# Sam7s64.net
KiCad netlist of a schematic drawn in EAGLE
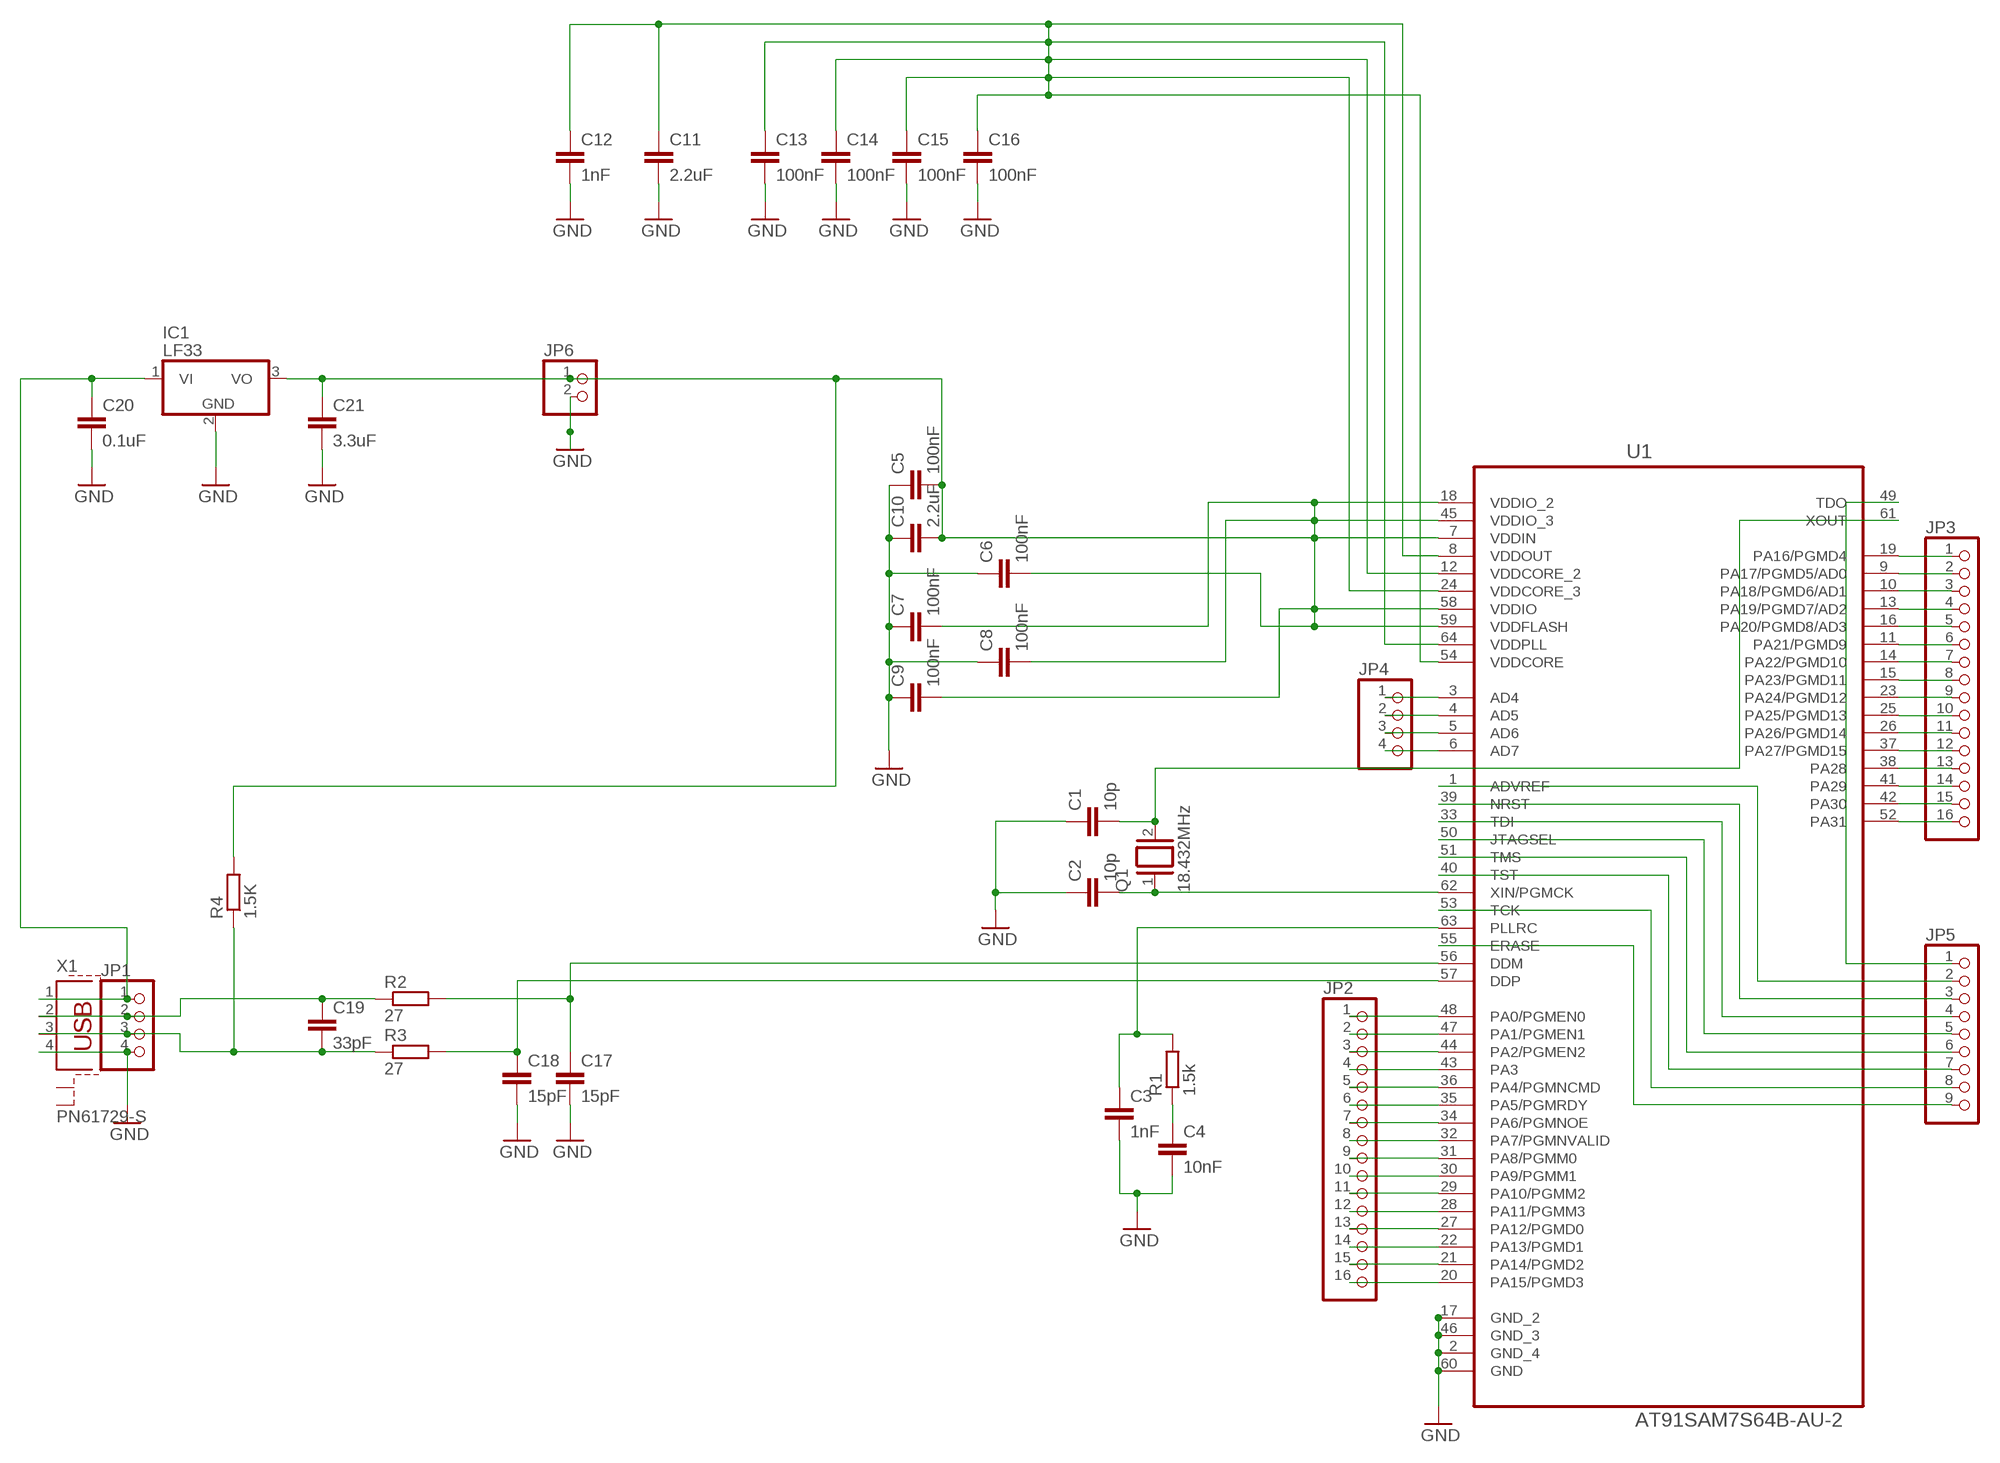
[diagram p0: schematic, sheet 1]

(export (version "E")
  (design (tool "Eeschema 10.0.6"))
  (components
    (comp (ref "C1")
      (value "10p")
      (footprint "eagle-import:C5B2.5")
      (libsource (lib "eagle-import") (part "C5/2.5"))
    )
    (comp (ref "C2")
      (value "10p")
      (footprint "eagle-import:C5B2.5")
      (libsource (lib "eagle-import") (part "C5/2.5"))
    )
    (comp (ref "C3")
      (value "1nF")
      (footprint "eagle-import:C5B2.5")
      (libsource (lib "eagle-import") (part "C5/2.5"))
    )
    (comp (ref "C4")
      (value "10nF")
      (footprint "eagle-import:C5B2.5")
      (libsource (lib "eagle-import") (part "C5/2.5"))
    )
    (comp (ref "C5")
      (value "100nF")
      (footprint "eagle-import:C5B2.5")
      (libsource (lib "eagle-import") (part "C5/2.5"))
    )
    (comp (ref "C6")
      (value "100nF")
      (footprint "eagle-import:C5B2.5")
      (libsource (lib "eagle-import") (part "C5/2.5"))
    )
    (comp (ref "C7")
      (value "100nF")
      (footprint "eagle-import:C5B2.5")
      (libsource (lib "eagle-import") (part "C5/2.5"))
    )
    (comp (ref "C8")
      (value "100nF")
      (footprint "eagle-import:C5B2.5")
      (libsource (lib "eagle-import") (part "C5/2.5"))
    )
    (comp (ref "C9")
      (value "100nF")
      (footprint "eagle-import:C5B2.5")
      (libsource (lib "eagle-import") (part "C5/2.5"))
    )
    (comp (ref "C10")
      (value "2.2uF")
      (footprint "eagle-import:C2.5-2")
      (libsource (lib "eagle-import") (part "C2.5/2"))
    )
    (comp (ref "C11")
      (value "2.2uF")
      (footprint "eagle-import:C2.5-2")
      (libsource (lib "eagle-import") (part "C2.5/2"))
    )
    (comp (ref "C12")
      (value "1nF")
      (footprint "eagle-import:C5B2.5")
      (libsource (lib "eagle-import") (part "C5/2.5"))
    )
    (comp (ref "C13")
      (value "100nF")
      (footprint "eagle-import:C5B2.5")
      (libsource (lib "eagle-import") (part "C5/2.5"))
    )
    (comp (ref "C14")
      (value "100nF")
      (footprint "eagle-import:C5B2.5")
      (libsource (lib "eagle-import") (part "C5/2.5"))
    )
    (comp (ref "C15")
      (value "100nF")
      (footprint "eagle-import:C5B2.5")
      (libsource (lib "eagle-import") (part "C5/2.5"))
    )
    (comp (ref "C16")
      (value "100nF")
      (footprint "eagle-import:C5B2.5")
      (libsource (lib "eagle-import") (part "C5/2.5"))
    )
    (comp (ref "C17")
      (value "15pF")
      (footprint "eagle-import:C5B2.5")
      (libsource (lib "eagle-import") (part "C5/2.5"))
    )
    (comp (ref "C18")
      (value "15pF")
      (footprint "eagle-import:C5B2.5")
      (libsource (lib "eagle-import") (part "C5/2.5"))
    )
    (comp (ref "C19")
      (value "33pF")
      (footprint "eagle-import:C5B2.5")
      (libsource (lib "eagle-import") (part "C5/2.5"))
    )
    (comp (ref "C20")
      (value "0.1uF")
      (footprint "eagle-import:C2.5-2")
      (libsource (lib "eagle-import") (part "C2.5/2"))
    )
    (comp (ref "C21")
      (value "3.3uF")
      (footprint "eagle-import:C2.5-2")
      (libsource (lib "eagle-import") (part "C2.5/2"))
    )
    (comp (ref "IC1")
      (value "LF33")
      (footprint "eagle-import:TO220V")
      (libsource (lib "eagle-import") (part "78TV05"))
    )
    (comp (ref "JP1")
      (value "PINHD-1X4")
      (footprint "eagle-import:1X04")
      (libsource (lib "eagle-import") (part "PINHD-1X4"))
    )
    (comp (ref "JP2")
      (value "PINHD-1X16")
      (footprint "eagle-import:1X16")
      (libsource (lib "eagle-import") (part "PINHD-1X16"))
    )
    (comp (ref "JP3")
      (value "PINHD-1X16")
      (footprint "eagle-import:1X16")
      (libsource (lib "eagle-import") (part "PINHD-1X16"))
    )
    (comp (ref "JP4")
      (value "PINHD-1X4")
      (footprint "eagle-import:1X04")
      (libsource (lib "eagle-import") (part "PINHD-1X4"))
    )
    (comp (ref "JP5")
      (value "PINHD-1X9")
      (footprint "eagle-import:1X09")
      (libsource (lib "eagle-import") (part "PINHD-1X9"))
    )
    (comp (ref "JP6")
      (value "PINHD-1X2")
      (footprint "eagle-import:1X02")
      (libsource (lib "eagle-import") (part "PINHD-1X2"))
    )
    (comp (ref "Q1")
      (value "18.432MHz")
      (footprint "eagle-import:QS")
      (libsource (lib "eagle-import") (part "XTAL/S"))
    )
    (comp (ref "R1")
      (value "1.5k")
      (footprint "eagle-import:0207_10")
      (libsource (lib "eagle-import") (part "R-EU_0207/10"))
    )
    (comp (ref "R2")
      (value "27")
      (footprint "eagle-import:0207_10")
      (libsource (lib "eagle-import") (part "R-EU_0207/10"))
    )
    (comp (ref "R3")
      (value "27")
      (footprint "eagle-import:0207_10")
      (libsource (lib "eagle-import") (part "R-EU_0207/10"))
    )
    (comp (ref "R4")
      (value "1.5K")
      (footprint "eagle-import:0207_10")
      (libsource (lib "eagle-import") (part "R-EU_0207/10"))
    )
    (comp (ref "U1")
      (value "AT91SAM7S64B-AU-2")
      (footprint "eagle-import:QFP50P1200X1200X160-64N")
      (fields (field (name "MPN") "AT91SAM7S64B-AU"))
      (libsource (lib "eagle-import") (part "AT91SAM7S64B-AU-2"))
    )
    (comp (ref "X1")
      (value "PN61729-S")
      (footprint "eagle-import:PN61729-S")
      (libsource (lib "eagle-import") (part "PN61729-S"))
    )
  )
  (nets
    (net (code "1") (name "GND") (class "Default")
      (node (ref "C1") (pin "1") (pinfunction "1_1") (pintype "passive"))
      (node (ref "C10") (pin "1") (pinfunction "1_1") (pintype "passive"))
      (node (ref "C11") (pin "2") (pinfunction "2_2") (pintype "passive"))
      (node (ref "C12") (pin "2") (pinfunction "2_2") (pintype "passive"))
      (node (ref "C13") (pin "2") (pinfunction "2_2") (pintype "passive"))
      (node (ref "C14") (pin "2") (pinfunction "2_2") (pintype "passive"))
      (node (ref "C15") (pin "2") (pinfunction "2_2") (pintype "passive"))
      (node (ref "C16") (pin "2") (pinfunction "2_2") (pintype "passive"))
      (node (ref "C17") (pin "2") (pinfunction "2_2") (pintype "passive"))
      (node (ref "C18") (pin "2") (pinfunction "2_2") (pintype "passive"))
      (node (ref "C2") (pin "1") (pinfunction "1_1") (pintype "passive"))
      (node (ref "C20") (pin "2") (pinfunction "2_2") (pintype "passive"))
      (node (ref "C21") (pin "2") (pinfunction "2_2") (pintype "passive"))
      (node (ref "C3") (pin "2") (pinfunction "2_2") (pintype "passive"))
      (node (ref "C4") (pin "2") (pinfunction "2_2") (pintype "passive"))
      (node (ref "C5") (pin "1") (pinfunction "1_1") (pintype "passive"))
      (node (ref "C6") (pin "1") (pinfunction "1_1") (pintype "passive"))
      (node (ref "C7") (pin "1") (pinfunction "1_1") (pintype "passive"))
      (node (ref "C8") (pin "1") (pinfunction "1_1") (pintype "passive"))
      (node (ref "C9") (pin "1") (pinfunction "1_1") (pintype "passive"))
      (node (ref "IC1") (pin "2") (pinfunction "GND_2") (pintype "passive"))
      (node (ref "JP1") (pin "4") (pinfunction "4_4") (pintype "passive"))
      (node (ref "JP6") (pin "2") (pinfunction "2_2") (pintype "passive"))
      (node (ref "U1") (pin "17") (pinfunction "GND_2_17") (pintype "passive"))
      (node (ref "U1") (pin "2") (pinfunction "GND_4_2") (pintype "passive"))
      (node (ref "U1") (pin "46") (pinfunction "GND_3_46") (pintype "passive"))
      (node (ref "U1") (pin "60") (pinfunction "GND_60") (pintype "passive"))
      (node (ref "X1") (pin "4") (pinfunction "4_4") (pintype "passive"))
    )
    (net (code "2") (name "Net-(C4-Pad1)") (class "Default")
      (node (ref "C4") (pin "1") (pinfunction "1_1") (pintype "passive"))
      (node (ref "R1") (pin "1") (pinfunction "1_1") (pintype "passive"))
    )
    (net (code "3") (name "Net-(C19-Pad1)") (class "Default")
      (node (ref "C19") (pin "1") (pinfunction "1_1") (pintype "passive"))
      (node (ref "JP1") (pin "2") (pinfunction "2_2") (pintype "passive"))
      (node (ref "R2") (pin "1") (pinfunction "1_1") (pintype "passive"))
      (node (ref "X1") (pin "2") (pinfunction "2_2") (pintype "passive"))
    )
    (net (code "4") (name "Net-(C19-Pad2)") (class "Default")
      (node (ref "C19") (pin "2") (pinfunction "2_2") (pintype "passive"))
      (node (ref "JP1") (pin "3") (pinfunction "3_3") (pintype "passive"))
      (node (ref "R3") (pin "1") (pinfunction "1_1") (pintype "passive"))
      (node (ref "R4") (pin "1") (pinfunction "1_1") (pintype "passive"))
      (node (ref "X1") (pin "3") (pinfunction "3_3") (pintype "passive"))
    )
    (net (code "5") (name "Net-(IC1-VI)") (class "Default")
      (node (ref "C20") (pin "1") (pinfunction "1_1") (pintype "passive"))
      (node (ref "IC1") (pin "1") (pinfunction "VI_1") (pintype "input"))
      (node (ref "JP1") (pin "1") (pinfunction "1_1") (pintype "passive"))
      (node (ref "X1") (pin "1") (pinfunction "1_1") (pintype "passive"))
    )
    (net (code "6") (name "Net-(IC1-VO)") (class "Default")
      (node (ref "C10") (pin "2") (pinfunction "2_2") (pintype "passive"))
      (node (ref "C21") (pin "1") (pinfunction "1_1") (pintype "passive"))
      (node (ref "C5") (pin "2") (pinfunction "2_2") (pintype "passive"))
      (node (ref "C6") (pin "2") (pinfunction "2_2") (pintype "passive"))
      (node (ref "C7") (pin "2") (pinfunction "2_2") (pintype "passive"))
      (node (ref "C8") (pin "2") (pinfunction "2_2") (pintype "passive"))
      (node (ref "C9") (pin "2") (pinfunction "2_2") (pintype "passive"))
      (node (ref "IC1") (pin "3") (pinfunction "VO_3") (pintype "passive"))
      (node (ref "JP6") (pin "1") (pinfunction "1_1") (pintype "passive"))
      (node (ref "R4") (pin "2") (pinfunction "2_2") (pintype "passive"))
      (node (ref "U1") (pin "18") (pinfunction "VDDIO_2_18") (pintype "power_in"))
      (node (ref "U1") (pin "45") (pinfunction "VDDIO_3_45") (pintype "power_in"))
      (node (ref "U1") (pin "58") (pinfunction "VDDIO_58") (pintype "power_in"))
      (node (ref "U1") (pin "59") (pinfunction "VDDFLASH_59") (pintype "power_in"))
      (node (ref "U1") (pin "7") (pinfunction "VDDIN_7") (pintype "power_in"))
    )
    (net (code "7") (name "Net-(U1-AD4)") (class "Default")
      (node (ref "JP4") (pin "1") (pinfunction "1_1") (pintype "passive"))
      (node (ref "U1") (pin "3") (pinfunction "AD4_3") (pintype "input"))
    )
    (net (code "8") (name "Net-(U1-AD5)") (class "Default")
      (node (ref "JP4") (pin "2") (pinfunction "2_2") (pintype "passive"))
      (node (ref "U1") (pin "4") (pinfunction "AD5_4") (pintype "input"))
    )
    (net (code "9") (name "Net-(U1-AD6)") (class "Default")
      (node (ref "JP4") (pin "3") (pinfunction "3_3") (pintype "passive"))
      (node (ref "U1") (pin "5") (pinfunction "AD6_5") (pintype "input"))
    )
    (net (code "10") (name "Net-(U1-AD7)") (class "Default")
      (node (ref "JP4") (pin "4") (pinfunction "4_4") (pintype "passive"))
      (node (ref "U1") (pin "6") (pinfunction "AD7_6") (pintype "input"))
    )
    (net (code "11") (name "Net-(U1-ADVREF)") (class "Default")
      (node (ref "JP5") (pin "2") (pinfunction "2_2") (pintype "passive"))
      (node (ref "U1") (pin "1") (pinfunction "ADVREF_1") (pintype "input"))
    )
    (net (code "12") (name "Net-(U1-DDM)") (class "Default")
      (node (ref "C17") (pin "1") (pinfunction "1_1") (pintype "passive"))
      (node (ref "R2") (pin "2") (pinfunction "2_2") (pintype "passive"))
      (node (ref "U1") (pin "56") (pinfunction "DDM_56") (pintype "input"))
    )
    (net (code "13") (name "Net-(U1-DDP)") (class "Default")
      (node (ref "C18") (pin "1") (pinfunction "1_1") (pintype "passive"))
      (node (ref "R3") (pin "2") (pinfunction "2_2") (pintype "passive"))
      (node (ref "U1") (pin "57") (pinfunction "DDP_57") (pintype "input"))
    )
    (net (code "14") (name "Net-(U1-ERASE)") (class "Default")
      (node (ref "JP5") (pin "9") (pinfunction "9_9") (pintype "passive"))
      (node (ref "U1") (pin "55") (pinfunction "ERASE_55") (pintype "input"))
    )
    (net (code "15") (name "Net-(U1-JTAGSEL)") (class "Default")
      (node (ref "JP5") (pin "5") (pinfunction "5_5") (pintype "passive"))
      (node (ref "U1") (pin "50") (pinfunction "JTAGSEL_50") (pintype "passive"))
    )
    (net (code "16") (name "Net-(U1-NRST)") (class "Default")
      (node (ref "JP5") (pin "3") (pinfunction "3_3") (pintype "passive"))
      (node (ref "U1") (pin "39") (pinfunction "NRST_39") (pintype "input"))
    )
    (net (code "17") (name "Net-(U1-PA0{slash}PGMEN0)") (class "Default")
      (node (ref "JP2") (pin "1") (pinfunction "1_1") (pintype "passive"))
      (node (ref "U1") (pin "48") (pinfunction "PA0/PGMEN0_48") (pintype "bidirectional"))
    )
    (net (code "18") (name "Net-(U1-PA1{slash}PGMEN1)") (class "Default")
      (node (ref "JP2") (pin "2") (pinfunction "2_2") (pintype "passive"))
      (node (ref "U1") (pin "47") (pinfunction "PA1/PGMEN1_47") (pintype "bidirectional"))
    )
    (net (code "19") (name "Net-(U1-PA2{slash}PGMEN2)") (class "Default")
      (node (ref "JP2") (pin "3") (pinfunction "3_3") (pintype "passive"))
      (node (ref "U1") (pin "44") (pinfunction "PA2/PGMEN2_44") (pintype "bidirectional"))
    )
    (net (code "20") (name "Net-(U1-PA3)") (class "Default")
      (node (ref "JP2") (pin "4") (pinfunction "4_4") (pintype "passive"))
      (node (ref "U1") (pin "43") (pinfunction "PA3_43") (pintype "bidirectional"))
    )
    (net (code "21") (name "Net-(U1-PA4{slash}PGMNCMD)") (class "Default")
      (node (ref "JP2") (pin "5") (pinfunction "5_5") (pintype "passive"))
      (node (ref "U1") (pin "36") (pinfunction "PA4/PGMNCMD_36") (pintype "bidirectional"))
    )
    (net (code "22") (name "Net-(U1-PA5{slash}PGMRDY)") (class "Default")
      (node (ref "JP2") (pin "6") (pinfunction "6_6") (pintype "passive"))
      (node (ref "U1") (pin "35") (pinfunction "PA5/PGMRDY_35") (pintype "bidirectional"))
    )
    (net (code "23") (name "Net-(U1-PA6{slash}PGMNOE)") (class "Default")
      (node (ref "JP2") (pin "7") (pinfunction "7_7") (pintype "passive"))
      (node (ref "U1") (pin "34") (pinfunction "PA6/PGMNOE_34") (pintype "bidirectional"))
    )
    (net (code "24") (name "Net-(U1-PA7{slash}PGMNVALID)") (class "Default")
      (node (ref "JP2") (pin "8") (pinfunction "8_8") (pintype "passive"))
      (node (ref "U1") (pin "32") (pinfunction "PA7/PGMNVALID_32") (pintype "bidirectional"))
    )
    (net (code "25") (name "Net-(U1-PA8{slash}PGMM0)") (class "Default")
      (node (ref "JP2") (pin "9") (pinfunction "9_9") (pintype "passive"))
      (node (ref "U1") (pin "31") (pinfunction "PA8/PGMM0_31") (pintype "bidirectional"))
    )
    (net (code "26") (name "Net-(U1-PA9{slash}PGMM1)") (class "Default")
      (node (ref "JP2") (pin "10") (pinfunction "10_10") (pintype "passive"))
      (node (ref "U1") (pin "30") (pinfunction "PA9/PGMM1_30") (pintype "bidirectional"))
    )
    (net (code "27") (name "Net-(U1-PA10{slash}PGMM2)") (class "Default")
      (node (ref "JP2") (pin "11") (pinfunction "11_11") (pintype "passive"))
      (node (ref "U1") (pin "29") (pinfunction "PA10/PGMM2_29") (pintype "bidirectional"))
    )
    (net (code "28") (name "Net-(U1-PA11{slash}PGMM3)") (class "Default")
      (node (ref "JP2") (pin "12") (pinfunction "12_12") (pintype "passive"))
      (node (ref "U1") (pin "28") (pinfunction "PA11/PGMM3_28") (pintype "bidirectional"))
    )
    (net (code "29") (name "Net-(U1-PA12{slash}PGMD0)") (class "Default")
      (node (ref "JP2") (pin "13") (pinfunction "13_13") (pintype "passive"))
      (node (ref "U1") (pin "27") (pinfunction "PA12/PGMD0_27") (pintype "bidirectional"))
    )
    (net (code "30") (name "Net-(U1-PA13{slash}PGMD1)") (class "Default")
      (node (ref "JP2") (pin "14") (pinfunction "14_14") (pintype "passive"))
      (node (ref "U1") (pin "22") (pinfunction "PA13/PGMD1_22") (pintype "bidirectional"))
    )
    (net (code "31") (name "Net-(U1-PA14{slash}PGMD2)") (class "Default")
      (node (ref "JP2") (pin "15") (pinfunction "15_15") (pintype "passive"))
      (node (ref "U1") (pin "21") (pinfunction "PA14/PGMD2_21") (pintype "bidirectional"))
    )
    (net (code "32") (name "Net-(U1-PA15{slash}PGMD3)") (class "Default")
      (node (ref "JP2") (pin "16") (pinfunction "16_16") (pintype "passive"))
      (node (ref "U1") (pin "20") (pinfunction "PA15/PGMD3_20") (pintype "bidirectional"))
    )
    (net (code "33") (name "Net-(U1-PA16{slash}PGMD4)") (class "Default")
      (node (ref "JP3") (pin "1") (pinfunction "1_1") (pintype "passive"))
      (node (ref "U1") (pin "19") (pinfunction "PA16/PGMD4_19") (pintype "bidirectional"))
    )
    (net (code "34") (name "Net-(U1-PA17{slash}PGMD5{slash}AD0)") (class "Default")
      (node (ref "JP3") (pin "2") (pinfunction "2_2") (pintype "passive"))
      (node (ref "U1") (pin "9") (pinfunction "PA17/PGMD5/AD0_9") (pintype "bidirectional"))
    )
    (net (code "35") (name "Net-(U1-PA18{slash}PGMD6{slash}AD1)") (class "Default")
      (node (ref "JP3") (pin "3") (pinfunction "3_3") (pintype "passive"))
      (node (ref "U1") (pin "10") (pinfunction "PA18/PGMD6/AD1_10") (pintype "bidirectional"))
    )
    (net (code "36") (name "Net-(U1-PA19{slash}PGMD7{slash}AD2)") (class "Default")
      (node (ref "JP3") (pin "4") (pinfunction "4_4") (pintype "passive"))
      (node (ref "U1") (pin "13") (pinfunction "PA19/PGMD7/AD2_13") (pintype "bidirectional"))
    )
    (net (code "37") (name "Net-(U1-PA20{slash}PGMD8{slash}AD3)") (class "Default")
      (node (ref "JP3") (pin "5") (pinfunction "5_5") (pintype "passive"))
      (node (ref "U1") (pin "16") (pinfunction "PA20/PGMD8/AD3_16") (pintype "bidirectional"))
    )
    (net (code "38") (name "Net-(U1-PA21{slash}PGMD9)") (class "Default")
      (node (ref "JP3") (pin "6") (pinfunction "6_6") (pintype "passive"))
      (node (ref "U1") (pin "11") (pinfunction "PA21/PGMD9_11") (pintype "bidirectional"))
    )
    (net (code "39") (name "Net-(U1-PA22{slash}PGMD10)") (class "Default")
      (node (ref "JP3") (pin "7") (pinfunction "7_7") (pintype "passive"))
      (node (ref "U1") (pin "14") (pinfunction "PA22/PGMD10_14") (pintype "bidirectional"))
    )
    (net (code "40") (name "Net-(U1-PA23{slash}PGMD11)") (class "Default")
      (node (ref "JP3") (pin "8") (pinfunction "8_8") (pintype "passive"))
      (node (ref "U1") (pin "15") (pinfunction "PA23/PGMD11_15") (pintype "bidirectional"))
    )
    (net (code "41") (name "Net-(U1-PA24{slash}PGMD12)") (class "Default")
      (node (ref "JP3") (pin "9") (pinfunction "9_9") (pintype "passive"))
      (node (ref "U1") (pin "23") (pinfunction "PA24/PGMD12_23") (pintype "bidirectional"))
    )
    (net (code "42") (name "Net-(U1-PA25{slash}PGMD13)") (class "Default")
      (node (ref "JP3") (pin "10") (pinfunction "10_10") (pintype "passive"))
      (node (ref "U1") (pin "25") (pinfunction "PA25/PGMD13_25") (pintype "bidirectional"))
    )
    (net (code "43") (name "Net-(U1-PA26{slash}PGMD14)") (class "Default")
      (node (ref "JP3") (pin "11") (pinfunction "11_11") (pintype "passive"))
      (node (ref "U1") (pin "26") (pinfunction "PA26/PGMD14_26") (pintype "bidirectional"))
    )
    (net (code "44") (name "Net-(U1-PA27{slash}PGMD15)") (class "Default")
      (node (ref "JP3") (pin "12") (pinfunction "12_12") (pintype "passive"))
      (node (ref "U1") (pin "37") (pinfunction "PA27/PGMD15_37") (pintype "bidirectional"))
    )
    (net (code "45") (name "Net-(U1-PA28)") (class "Default")
      (node (ref "JP3") (pin "13") (pinfunction "13_13") (pintype "passive"))
      (node (ref "U1") (pin "38") (pinfunction "PA28_38") (pintype "bidirectional"))
    )
    (net (code "46") (name "Net-(U1-PA29)") (class "Default")
      (node (ref "JP3") (pin "14") (pinfunction "14_14") (pintype "passive"))
      (node (ref "U1") (pin "41") (pinfunction "PA29_41") (pintype "bidirectional"))
    )
    (net (code "47") (name "Net-(U1-PA30)") (class "Default")
      (node (ref "JP3") (pin "15") (pinfunction "15_15") (pintype "passive"))
      (node (ref "U1") (pin "42") (pinfunction "PA30_42") (pintype "bidirectional"))
    )
    (net (code "48") (name "Net-(U1-PA31)") (class "Default")
      (node (ref "JP3") (pin "16") (pinfunction "16_16") (pintype "passive"))
      (node (ref "U1") (pin "52") (pinfunction "PA31_52") (pintype "bidirectional"))
    )
    (net (code "49") (name "Net-(U1-PLLRC)") (class "Default")
      (node (ref "C3") (pin "1") (pinfunction "1_1") (pintype "passive"))
      (node (ref "R1") (pin "2") (pinfunction "2_2") (pintype "passive"))
      (node (ref "U1") (pin "63") (pinfunction "PLLRC_63") (pintype "passive"))
    )
    (net (code "50") (name "Net-(U1-TCK)") (class "Default")
      (node (ref "JP5") (pin "8") (pinfunction "8_8") (pintype "passive"))
      (node (ref "U1") (pin "53") (pinfunction "TCK_53") (pintype "input"))
    )
    (net (code "51") (name "Net-(U1-TDI)") (class "Default")
      (node (ref "JP5") (pin "4") (pinfunction "4_4") (pintype "passive"))
      (node (ref "U1") (pin "33") (pinfunction "TDI_33") (pintype "input"))
    )
    (net (code "52") (name "Net-(U1-TDO)") (class "Default")
      (node (ref "JP5") (pin "1") (pinfunction "1_1") (pintype "passive"))
      (node (ref "U1") (pin "49") (pinfunction "TDO_49") (pintype "bidirectional"))
    )
    (net (code "53") (name "Net-(U1-TMS)") (class "Default")
      (node (ref "JP5") (pin "6") (pinfunction "6_6") (pintype "passive"))
      (node (ref "U1") (pin "51") (pinfunction "TMS_51") (pintype "input"))
    )
    (net (code "54") (name "Net-(U1-TST)") (class "Default")
      (node (ref "JP5") (pin "7") (pinfunction "7_7") (pintype "passive"))
      (node (ref "U1") (pin "40") (pinfunction "TST_40") (pintype "input"))
    )
    (net (code "55") (name "Net-(U1-VDDCORE)") (class "Default")
      (node (ref "C11") (pin "1") (pinfunction "1_1") (pintype "passive"))
      (node (ref "C12") (pin "1") (pinfunction "1_1") (pintype "passive"))
      (node (ref "C13") (pin "1") (pinfunction "1_1") (pintype "passive"))
      (node (ref "C14") (pin "1") (pinfunction "1_1") (pintype "passive"))
      (node (ref "C15") (pin "1") (pinfunction "1_1") (pintype "passive"))
      (node (ref "C16") (pin "1") (pinfunction "1_1") (pintype "passive"))
      (node (ref "U1") (pin "12") (pinfunction "VDDCORE_2_12") (pintype "power_in"))
      (node (ref "U1") (pin "24") (pinfunction "VDDCORE_3_24") (pintype "power_in"))
      (node (ref "U1") (pin "54") (pinfunction "VDDCORE_54") (pintype "power_in"))
      (node (ref "U1") (pin "64") (pinfunction "VDDPLL_64") (pintype "power_in"))
      (node (ref "U1") (pin "8") (pinfunction "VDDOUT_8") (pintype "power_in"))
    )
    (net (code "56") (name "Net-(U1-XIN{slash}PGMCK)") (class "Default")
      (node (ref "C2") (pin "2") (pinfunction "2_2") (pintype "passive"))
      (node (ref "Q1") (pin "1") (pinfunction "1_1") (pintype "passive"))
      (node (ref "U1") (pin "62") (pinfunction "XIN/PGMCK_62") (pintype "input"))
    )
    (net (code "57") (name "Net-(U1-XOUT)") (class "Default")
      (node (ref "C1") (pin "2") (pinfunction "2_2") (pintype "passive"))
      (node (ref "Q1") (pin "2") (pinfunction "2_2") (pintype "passive"))
      (node (ref "U1") (pin "61") (pinfunction "XOUT_61") (pintype "output"))
    )
    (net (code "58") (name "unconnected-(X1-PadS1)") (class "Default")
      (node (ref "X1") (pin "S1") (pinfunction "S1_S1") (pintype "passive"))
    )
    (net (code "59") (name "unconnected-(X1-PadS2)") (class "Default")
      (node (ref "X1") (pin "S2") (pinfunction "S2_S2") (pintype "passive"))
    )
  )
)
